# MPU6050.net
KiCad netlist of a schematic drawn in Altium Designer
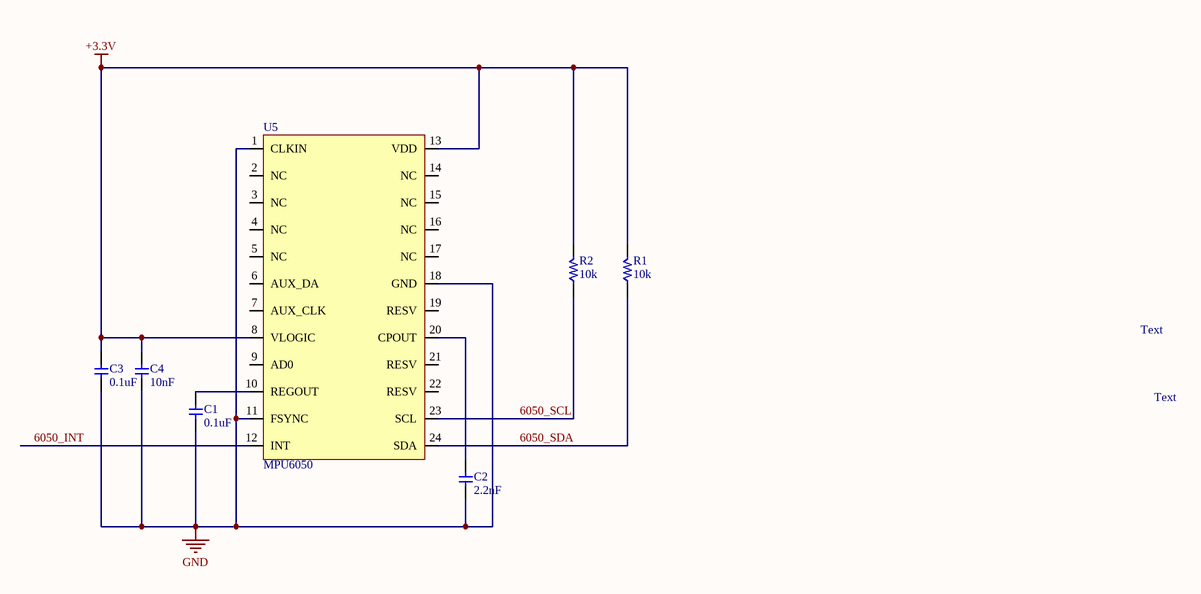
[diagram p0: MPU6050.SchDoc]

(export (version "E")
  (design (tool "Eeschema 10.0.6"))
  (components
    (comp (ref "C1")
      (value "0.1uF")
      (footprint "0805")
      (description "Generic capacitor")
      (fields (field (name "Comment") "Generic Capacitor"))
      (libsource (lib "PowerCircuit") (part "Capacitor"))
    )
    (comp (ref "C2")
      (value "2.2nF")
      (footprint "0805")
      (description "Generic capacitor")
      (fields (field (name "Comment") "Generic Capacitor"))
      (libsource (lib "PowerCircuit") (part "Capacitor"))
    )
    (comp (ref "C3")
      (value "0.1uF")
      (footprint "0805")
      (description "Generic capacitor")
      (fields (field (name "Comment") "Generic Capacitor"))
      (libsource (lib "PowerCircuit") (part "Capacitor"))
    )
    (comp (ref "C4")
      (value "10nF")
      (footprint "0805")
      (description "Generic capacitor")
      (fields (field (name "Comment") "Generic Capacitor"))
      (libsource (lib "PowerCircuit") (part "Capacitor"))
    )
    (comp (ref "R1")
      (value "10k")
      (footprint "0805")
      (description "Generic Resistor")
      (fields (field (name "Comment") "Resistor"))
      (libsource (lib "PowerCircuit") (part "Resistor"))
    )
    (comp (ref "R2")
      (value "10k")
      (footprint "0805")
      (description "Generic Resistor")
      (fields (field (name "Comment") "Resistor"))
      (libsource (lib "PowerCircuit") (part "Resistor"))
    )
    (comp (ref "U5")
      (value "MPU6050")
      (footprint "MPU-6050")
      (description "IMU ACCEL/GYRO 3-AXIS I2C 24QFN")
      (libsource (lib "MPU6050") (part "MPU6050"))
    )
  )
  (nets
    (net (code "1") (name "+3.3V") (class "Default")
      (node (ref "C3") (pin "1") (pinfunction "1_1") (pintype "passive"))
      (node (ref "C4") (pin "2") (pinfunction "2_2") (pintype "passive"))
      (node (ref "R1") (pin "2") (pinfunction "2_2") (pintype "passive"))
      (node (ref "R2") (pin "2") (pinfunction "2_2") (pintype "passive"))
      (node (ref "U5") (pin "13") (pinfunction "VDD_13") (pintype "passive"))
      (node (ref "U5") (pin "8") (pinfunction "VLOGIC_8") (pintype "passive"))
    )
    (net (code "2") (name "/6050_INT") (class "Default")
      (node (ref "U5") (pin "12") (pinfunction "INT_12") (pintype "passive"))
    )
    (net (code "3") (name "/6050_SCL") (class "Default")
      (node (ref "R2") (pin "1") (pinfunction "1_1") (pintype "passive"))
      (node (ref "U5") (pin "23") (pinfunction "SCL_23") (pintype "passive"))
    )
    (net (code "4") (name "/6050_SDA") (class "Default")
      (node (ref "R1") (pin "1") (pinfunction "1_1") (pintype "passive"))
      (node (ref "U5") (pin "24") (pinfunction "SDA_24") (pintype "passive"))
    )
    (net (code "5") (name "GND") (class "Default")
      (node (ref "C1") (pin "1") (pinfunction "1_1") (pintype "passive"))
      (node (ref "C2") (pin "1") (pinfunction "1_1") (pintype "passive"))
      (node (ref "C3") (pin "2") (pinfunction "2_2") (pintype "passive"))
      (node (ref "C4") (pin "1") (pinfunction "1_1") (pintype "passive"))
      (node (ref "U5") (pin "1") (pinfunction "CLKIN_1") (pintype "passive"))
      (node (ref "U5") (pin "11") (pinfunction "FSYNC_11") (pintype "passive"))
      (node (ref "U5") (pin "18") (pinfunction "GND_18") (pintype "passive"))
    )
    (net (code "6") (name "Net-(U5-CPOUT)") (class "Default")
      (node (ref "C2") (pin "2") (pinfunction "2_2") (pintype "passive"))
      (node (ref "U5") (pin "20") (pinfunction "CPOUT_20") (pintype "passive"))
    )
    (net (code "7") (name "Net-(U5-REGOUT)") (class "Default")
      (node (ref "C1") (pin "2") (pinfunction "2_2") (pintype "passive"))
      (node (ref "U5") (pin "10") (pinfunction "REGOUT_10") (pintype "passive"))
    )
    (net (code "8") (name "unconnected-(U5-AD0-Pad9)") (class "Default")
      (node (ref "U5") (pin "9") (pinfunction "AD0_9") (pintype "passive"))
    )
    (net (code "9") (name "unconnected-(U5-AUX_CLK-Pad7)") (class "Default")
      (node (ref "U5") (pin "7") (pinfunction "AUX_CLK_7") (pintype "passive"))
    )
    (net (code "10") (name "unconnected-(U5-AUX_DA-Pad6)") (class "Default")
      (node (ref "U5") (pin "6") (pinfunction "AUX_DA_6") (pintype "passive"))
    )
    (net (code "11") (name "unconnected-(U5-NC-Pad2)") (class "Default")
      (node (ref "U5") (pin "2") (pinfunction "NC_2") (pintype "passive"))
    )
    (net (code "12") (name "unconnected-(U5-NC-Pad3)") (class "Default")
      (node (ref "U5") (pin "3") (pinfunction "NC_3") (pintype "passive"))
    )
    (net (code "13") (name "unconnected-(U5-NC-Pad4)") (class "Default")
      (node (ref "U5") (pin "4") (pinfunction "NC_4") (pintype "passive"))
    )
    (net (code "14") (name "unconnected-(U5-NC-Pad5)") (class "Default")
      (node (ref "U5") (pin "5") (pinfunction "NC_5") (pintype "passive"))
    )
    (net (code "15") (name "unconnected-(U5-NC-Pad14)") (class "Default")
      (node (ref "U5") (pin "14") (pinfunction "NC_14") (pintype "passive"))
    )
    (net (code "16") (name "unconnected-(U5-NC-Pad15)") (class "Default")
      (node (ref "U5") (pin "15") (pinfunction "NC_15") (pintype "passive"))
    )
    (net (code "17") (name "unconnected-(U5-NC-Pad16)") (class "Default")
      (node (ref "U5") (pin "16") (pinfunction "NC_16") (pintype "passive"))
    )
    (net (code "18") (name "unconnected-(U5-NC-Pad17)") (class "Default")
      (node (ref "U5") (pin "17") (pinfunction "NC_17") (pintype "passive"))
    )
    (net (code "19") (name "unconnected-(U5-RESV-Pad19)") (class "Default")
      (node (ref "U5") (pin "19") (pinfunction "RESV_19") (pintype "passive"))
    )
    (net (code "20") (name "unconnected-(U5-RESV-Pad21)") (class "Default")
      (node (ref "U5") (pin "21") (pinfunction "RESV_21") (pintype "passive"))
    )
    (net (code "21") (name "unconnected-(U5-RESV-Pad22)") (class "Default")
      (node (ref "U5") (pin "22") (pinfunction "RESV_22") (pintype "passive"))
    )
  )
)
